# left.net
KiCad netlist of a schematic drawn in EAGLE
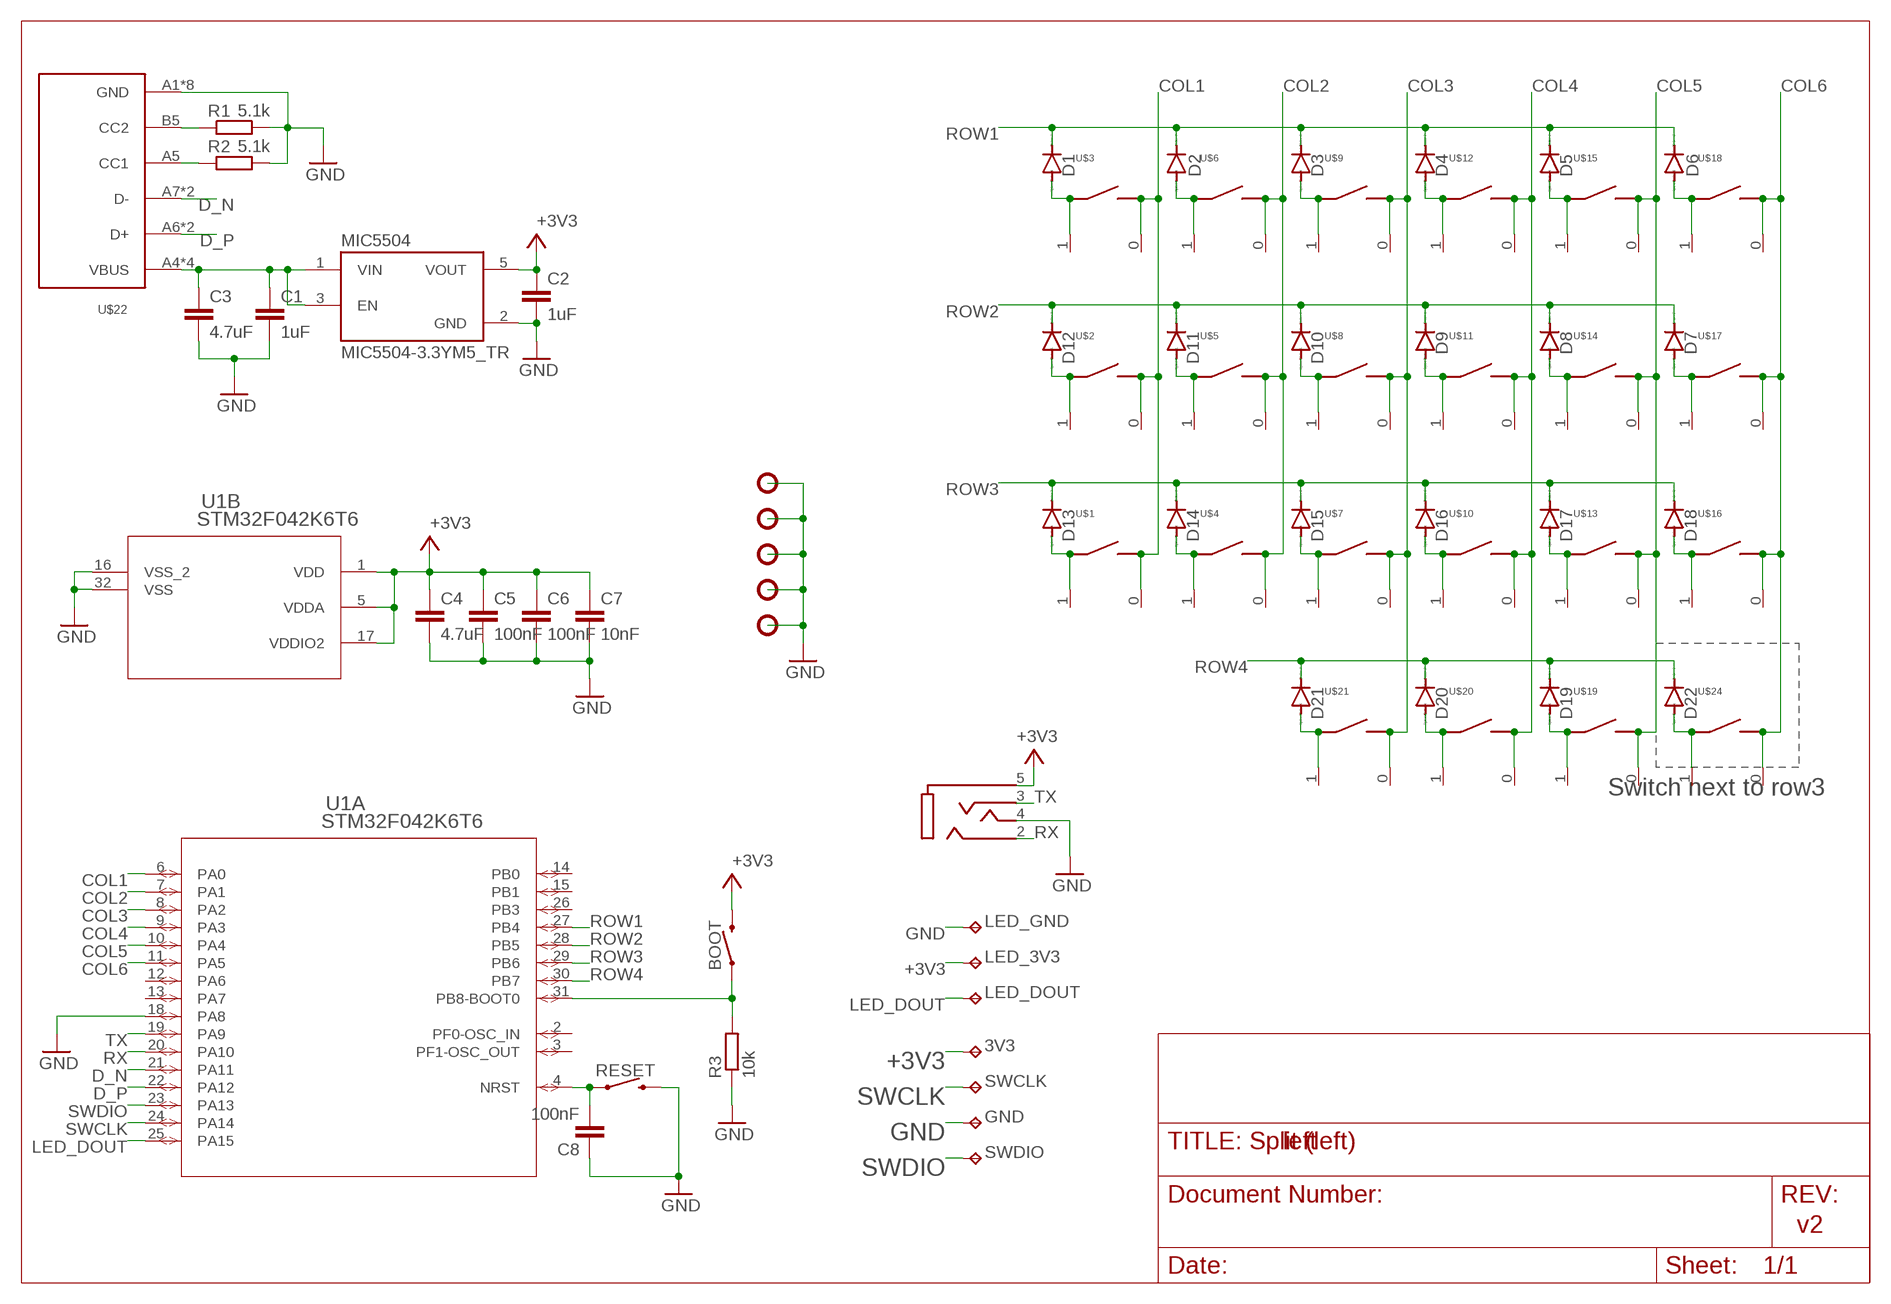
[diagram p0: schematic, sheet 1]

(export (version "E")
  (design (tool "Eeschema 10.0.6"))
  (components
    (comp (ref "3V3")
      (value "TPTP20R")
      (footprint "eagle-import:TP20R")
      (libsource (lib "eagle-import") (part "TPTP20R"))
    )
    (comp (ref "BOOT")
      (value "MOMENTARY-SWITCH-SPST-SMD-6.2MM-TALL")
      (footprint "eagle-import:TACTILE_SWITCH_SMD_6.2MM")
      (libsource (lib "eagle-import") (part "MOMENTARY-SWITCH-SPST-SMD-6.2MM-TALL"))
    )
    (comp (ref "C1")
      (value "1uF")
      (footprint "eagle-import:C0603")
      (libsource (lib "eagle-import") (part "C-EUC0603"))
    )
    (comp (ref "C2")
      (value "1uF")
      (footprint "eagle-import:C0603")
      (libsource (lib "eagle-import") (part "C-EUC0603"))
    )
    (comp (ref "C3")
      (value "4.7uF")
      (footprint "eagle-import:C0603")
      (libsource (lib "eagle-import") (part "C-EUC0603"))
    )
    (comp (ref "C4")
      (value "4.7uF")
      (footprint "eagle-import:C0603")
      (libsource (lib "eagle-import") (part "C-EUC0603"))
    )
    (comp (ref "C5")
      (value "100nF")
      (footprint "eagle-import:C0603")
      (libsource (lib "eagle-import") (part "C-EUC0603"))
    )
    (comp (ref "C6")
      (value "100nF")
      (footprint "eagle-import:C0603")
      (libsource (lib "eagle-import") (part "C-EUC0603"))
    )
    (comp (ref "C7")
      (value "10nF")
      (footprint "eagle-import:C0603")
      (libsource (lib "eagle-import") (part "C-EUC0603"))
    )
    (comp (ref "C8")
      (value "100nF")
      (footprint "eagle-import:C0603")
      (libsource (lib "eagle-import") (part "C-EUC0603"))
    )
    (comp (ref "D1")
      (value "DIODE-MINIMELF")
      (footprint "eagle-import:MINIMELF")
      (libsource (lib "eagle-import") (part "DIODE-MINIMELF"))
    )
    (comp (ref "D2")
      (value "DIODE-MINIMELF")
      (footprint "eagle-import:MINIMELF")
      (libsource (lib "eagle-import") (part "DIODE-MINIMELF"))
    )
    (comp (ref "D3")
      (value "DIODE-MINIMELF")
      (footprint "eagle-import:MINIMELF")
      (libsource (lib "eagle-import") (part "DIODE-MINIMELF"))
    )
    (comp (ref "D4")
      (value "DIODE-MINIMELF")
      (footprint "eagle-import:MINIMELF")
      (libsource (lib "eagle-import") (part "DIODE-MINIMELF"))
    )
    (comp (ref "D5")
      (value "DIODE-MINIMELF")
      (footprint "eagle-import:MINIMELF")
      (libsource (lib "eagle-import") (part "DIODE-MINIMELF"))
    )
    (comp (ref "D6")
      (value "DIODE-MINIMELF")
      (footprint "eagle-import:MINIMELF")
      (libsource (lib "eagle-import") (part "DIODE-MINIMELF"))
    )
    (comp (ref "D7")
      (value "DIODE-MINIMELF")
      (footprint "eagle-import:MINIMELF")
      (libsource (lib "eagle-import") (part "DIODE-MINIMELF"))
    )
    (comp (ref "D8")
      (value "DIODE-MINIMELF")
      (footprint "eagle-import:MINIMELF")
      (libsource (lib "eagle-import") (part "DIODE-MINIMELF"))
    )
    (comp (ref "D9")
      (value "DIODE-MINIMELF")
      (footprint "eagle-import:MINIMELF")
      (libsource (lib "eagle-import") (part "DIODE-MINIMELF"))
    )
    (comp (ref "D10")
      (value "DIODE-MINIMELF")
      (footprint "eagle-import:MINIMELF")
      (libsource (lib "eagle-import") (part "DIODE-MINIMELF"))
    )
    (comp (ref "D11")
      (value "DIODE-MINIMELF")
      (footprint "eagle-import:MINIMELF")
      (libsource (lib "eagle-import") (part "DIODE-MINIMELF"))
    )
    (comp (ref "D12")
      (value "DIODE-MINIMELF")
      (footprint "eagle-import:MINIMELF")
      (libsource (lib "eagle-import") (part "DIODE-MINIMELF"))
    )
    (comp (ref "D13")
      (value "DIODE-MINIMELF")
      (footprint "eagle-import:MINIMELF")
      (libsource (lib "eagle-import") (part "DIODE-MINIMELF"))
    )
    (comp (ref "D14")
      (value "DIODE-MINIMELF")
      (footprint "eagle-import:MINIMELF")
      (libsource (lib "eagle-import") (part "DIODE-MINIMELF"))
    )
    (comp (ref "D15")
      (value "DIODE-MINIMELF")
      (footprint "eagle-import:MINIMELF")
      (libsource (lib "eagle-import") (part "DIODE-MINIMELF"))
    )
    (comp (ref "D16")
      (value "DIODE-MINIMELF")
      (footprint "eagle-import:MINIMELF")
      (libsource (lib "eagle-import") (part "DIODE-MINIMELF"))
    )
    (comp (ref "D17")
      (value "DIODE-MINIMELF")
      (footprint "eagle-import:MINIMELF")
      (libsource (lib "eagle-import") (part "DIODE-MINIMELF"))
    )
    (comp (ref "D18")
      (value "DIODE-MINIMELF")
      (footprint "eagle-import:MINIMELF")
      (libsource (lib "eagle-import") (part "DIODE-MINIMELF"))
    )
    (comp (ref "D19")
      (value "DIODE-MINIMELF")
      (footprint "eagle-import:MINIMELF")
      (libsource (lib "eagle-import") (part "DIODE-MINIMELF"))
    )
    (comp (ref "D20")
      (value "DIODE-MINIMELF")
      (footprint "eagle-import:MINIMELF")
      (libsource (lib "eagle-import") (part "DIODE-MINIMELF"))
    )
    (comp (ref "D21")
      (value "DIODE-MINIMELF")
      (footprint "eagle-import:MINIMELF")
      (libsource (lib "eagle-import") (part "DIODE-MINIMELF"))
    )
    (comp (ref "D22")
      (value "DIODE-MINIMELF")
      (footprint "eagle-import:MINIMELF")
      (libsource (lib "eagle-import") (part "DIODE-MINIMELF"))
    )
    (comp (ref "GND")
      (value "TPTP20R")
      (footprint "eagle-import:TP20R")
      (libsource (lib "eagle-import") (part "TPTP20R"))
    )
    (comp (ref "LED_3V3")
      (value "TPTP20R")
      (footprint "eagle-import:TP20R")
      (libsource (lib "eagle-import") (part "TPTP20R"))
    )
    (comp (ref "LED_DOUT")
      (value "TPTP20R")
      (footprint "eagle-import:TP20R")
      (libsource (lib "eagle-import") (part "TPTP20R"))
    )
    (comp (ref "LED_GND")
      (value "TPTP20R")
      (footprint "eagle-import:TP20R")
      (libsource (lib "eagle-import") (part "TPTP20R"))
    )
    (comp (ref "MIC5504")
      (value "MIC5504-3.3YM5_TR")
      (footprint "eagle-import:SOT95P280X145-5N")
      (fields (field (name "MF") "Microchip") (field (name "MP") "MIC5504-3.3YM5 TR"))
      (libsource (lib "eagle-import") (part "MIC5504-3.3YM5_TR"))
    )
    (comp (ref "R1")
      (value "5.1k")
      (footprint "eagle-import:R0603")
      (libsource (lib "eagle-import") (part "R-EU_R0603"))
    )
    (comp (ref "R2")
      (value "5.1k")
      (footprint "eagle-import:R0603")
      (libsource (lib "eagle-import") (part "R-EU_R0603"))
    )
    (comp (ref "R3")
      (value "10k")
      (footprint "eagle-import:R0603")
      (libsource (lib "eagle-import") (part "R-EU_R0603"))
    )
    (comp (ref "RESET")
      (value "MOMENTARY-SWITCH-SPST-SMD-6.2MM-TALL")
      (footprint "eagle-import:TACTILE_SWITCH_SMD_6.2MM")
      (libsource (lib "eagle-import") (part "MOMENTARY-SWITCH-SPST-SMD-6.2MM-TALL"))
    )
    (comp (ref "SWCLK")
      (value "TPTP20R")
      (footprint "eagle-import:TP20R")
      (libsource (lib "eagle-import") (part "TPTP20R"))
    )
    (comp (ref "SWDIO")
      (value "TPTP20R")
      (footprint "eagle-import:TP20R")
      (libsource (lib "eagle-import") (part "TPTP20R"))
    )
    (comp (ref "U$1")
      (value "CHOC-CHOC-1U")
      (footprint "eagle-import:CHOC-1U")
      (libsource (lib "eagle-import") (part "CHOC-CHOC-1U"))
    )
    (comp (ref "U$2")
      (value "CHOC-CHOC-1U")
      (footprint "eagle-import:CHOC-1U")
      (libsource (lib "eagle-import") (part "CHOC-CHOC-1U"))
    )
    (comp (ref "U$3")
      (value "CHOC-CHOC-1U")
      (footprint "eagle-import:CHOC-1U")
      (libsource (lib "eagle-import") (part "CHOC-CHOC-1U"))
    )
    (comp (ref "U$4")
      (value "CHOC-CHOC-1U")
      (footprint "eagle-import:CHOC-1U")
      (libsource (lib "eagle-import") (part "CHOC-CHOC-1U"))
    )
    (comp (ref "U$5")
      (value "CHOC-CHOC-1U")
      (footprint "eagle-import:CHOC-1U")
      (libsource (lib "eagle-import") (part "CHOC-CHOC-1U"))
    )
    (comp (ref "U$6")
      (value "CHOC-CHOC-1U")
      (footprint "eagle-import:CHOC-1U")
      (libsource (lib "eagle-import") (part "CHOC-CHOC-1U"))
    )
    (comp (ref "U$7")
      (value "CHOC-CHOC-1U")
      (footprint "eagle-import:CHOC-1U")
      (libsource (lib "eagle-import") (part "CHOC-CHOC-1U"))
    )
    (comp (ref "U$8")
      (value "CHOC-CHOC-1U")
      (footprint "eagle-import:CHOC-1U")
      (libsource (lib "eagle-import") (part "CHOC-CHOC-1U"))
    )
    (comp (ref "U$9")
      (value "CHOC-CHOC-1U")
      (footprint "eagle-import:CHOC-1U")
      (libsource (lib "eagle-import") (part "CHOC-CHOC-1U"))
    )
    (comp (ref "U$10")
      (value "CHOC-CHOC-1U")
      (footprint "eagle-import:CHOC-1U")
      (libsource (lib "eagle-import") (part "CHOC-CHOC-1U"))
    )
    (comp (ref "U$11")
      (value "CHOC-CHOC-1U")
      (footprint "eagle-import:CHOC-1U")
      (libsource (lib "eagle-import") (part "CHOC-CHOC-1U"))
    )
    (comp (ref "U$12")
      (value "CHOC-CHOC-1U")
      (footprint "eagle-import:CHOC-1U")
      (libsource (lib "eagle-import") (part "CHOC-CHOC-1U"))
    )
    (comp (ref "U$13")
      (value "CHOC-CHOC-1U")
      (footprint "eagle-import:CHOC-1U")
      (libsource (lib "eagle-import") (part "CHOC-CHOC-1U"))
    )
    (comp (ref "U$14")
      (value "CHOC-CHOC-1U")
      (footprint "eagle-import:CHOC-1U")
      (libsource (lib "eagle-import") (part "CHOC-CHOC-1U"))
    )
    (comp (ref "U$15")
      (value "CHOC-CHOC-1U")
      (footprint "eagle-import:CHOC-1U")
      (libsource (lib "eagle-import") (part "CHOC-CHOC-1U"))
    )
    (comp (ref "U$16")
      (value "CHOC-CHOC-1U")
      (footprint "eagle-import:CHOC-1U")
      (libsource (lib "eagle-import") (part "CHOC-CHOC-1U"))
    )
    (comp (ref "U$17")
      (value "CHOC-CHOC-1U")
      (footprint "eagle-import:CHOC-1U")
      (libsource (lib "eagle-import") (part "CHOC-CHOC-1U"))
    )
    (comp (ref "U$18")
      (value "CHOC-CHOC-1U")
      (footprint "eagle-import:CHOC-1U")
      (libsource (lib "eagle-import") (part "CHOC-CHOC-1U"))
    )
    (comp (ref "U$19")
      (value "CHOC-CHOC-1U")
      (footprint "eagle-import:CHOC-1U")
      (libsource (lib "eagle-import") (part "CHOC-CHOC-1U"))
    )
    (comp (ref "U$20")
      (value "CHOC-CHOC-1U")
      (footprint "eagle-import:CHOC-1U")
      (libsource (lib "eagle-import") (part "CHOC-CHOC-1U"))
    )
    (comp (ref "U$21")
      (value "CHOC-CHOC-1U")
      (footprint "eagle-import:CHOC-1U")
      (libsource (lib "eagle-import") (part "CHOC-CHOC-1U"))
    )
    (comp (ref "U$22")
      (value "217B-AG01")
      (footprint "eagle-import:217B-AG01")
      (libsource (lib "eagle-import") (part "217B-AG01"))
    )
    (comp (ref "U$23")
      (value "PJ320A")
      (footprint "eagle-import:PJ320A")
      (libsource (lib "eagle-import") (part "PJ320A"))
    )
    (comp (ref "U$24")
      (value "CHOC-CHOC-1U")
      (footprint "eagle-import:CHOC-1U")
      (libsource (lib "eagle-import") (part "CHOC-CHOC-1U"))
    )
    (comp (ref "U$25")
      (value "SOCKET")
      (footprint "eagle-import:CHOC-SOCKET")
      (libsource (lib "eagle-import") (part "SOCKET"))
    )
    (comp (ref "U$26")
      (value "SOCKET")
      (footprint "eagle-import:CHOC-SOCKET")
      (libsource (lib "eagle-import") (part "SOCKET"))
    )
    (comp (ref "U$27")
      (value "SOCKET")
      (footprint "eagle-import:CHOC-SOCKET")
      (libsource (lib "eagle-import") (part "SOCKET"))
    )
    (comp (ref "U$28")
      (value "SOCKET")
      (footprint "eagle-import:CHOC-SOCKET")
      (libsource (lib "eagle-import") (part "SOCKET"))
    )
    (comp (ref "U$29")
      (value "SOCKET")
      (footprint "eagle-import:CHOC-SOCKET")
      (libsource (lib "eagle-import") (part "SOCKET"))
    )
    (comp (ref "U$30")
      (value "SOCKET")
      (footprint "eagle-import:CHOC-SOCKET")
      (libsource (lib "eagle-import") (part "SOCKET"))
    )
    (comp (ref "U$31")
      (value "SOCKET")
      (footprint "eagle-import:CHOC-SOCKET")
      (libsource (lib "eagle-import") (part "SOCKET"))
    )
    (comp (ref "U$32")
      (value "SOCKET")
      (footprint "eagle-import:CHOC-SOCKET")
      (libsource (lib "eagle-import") (part "SOCKET"))
    )
    (comp (ref "U$33")
      (value "SOCKET")
      (footprint "eagle-import:CHOC-SOCKET")
      (libsource (lib "eagle-import") (part "SOCKET"))
    )
    (comp (ref "U$34")
      (value "SOCKET")
      (footprint "eagle-import:CHOC-SOCKET")
      (libsource (lib "eagle-import") (part "SOCKET"))
    )
    (comp (ref "U$35")
      (value "SOCKET")
      (footprint "eagle-import:CHOC-SOCKET")
      (libsource (lib "eagle-import") (part "SOCKET"))
    )
    (comp (ref "U$36")
      (value "SOCKET")
      (footprint "eagle-import:CHOC-SOCKET")
      (libsource (lib "eagle-import") (part "SOCKET"))
    )
    (comp (ref "U$37")
      (value "SOCKET")
      (footprint "eagle-import:CHOC-SOCKET")
      (libsource (lib "eagle-import") (part "SOCKET"))
    )
    (comp (ref "U$38")
      (value "SOCKET")
      (footprint "eagle-import:CHOC-SOCKET")
      (libsource (lib "eagle-import") (part "SOCKET"))
    )
    (comp (ref "U$39")
      (value "SOCKET")
      (footprint "eagle-import:CHOC-SOCKET")
      (libsource (lib "eagle-import") (part "SOCKET"))
    )
    (comp (ref "U$40")
      (value "SOCKET")
      (footprint "eagle-import:CHOC-SOCKET")
      (libsource (lib "eagle-import") (part "SOCKET"))
    )
    (comp (ref "U$41")
      (value "SOCKET")
      (footprint "eagle-import:CHOC-SOCKET")
      (libsource (lib "eagle-import") (part "SOCKET"))
    )
    (comp (ref "U$42")
      (value "SOCKET")
      (footprint "eagle-import:CHOC-SOCKET")
      (libsource (lib "eagle-import") (part "SOCKET"))
    )
    (comp (ref "U$43")
      (value "SOCKET")
      (footprint "eagle-import:CHOC-SOCKET")
      (libsource (lib "eagle-import") (part "SOCKET"))
    )
    (comp (ref "U$44")
      (value "SOCKET")
      (footprint "eagle-import:CHOC-SOCKET")
      (libsource (lib "eagle-import") (part "SOCKET"))
    )
    (comp (ref "U$45")
      (value "SOCKET")
      (footprint "eagle-import:CHOC-SOCKET")
      (libsource (lib "eagle-import") (part "SOCKET"))
    )
    (comp (ref "U$46")
      (value "SOCKET")
      (footprint "eagle-import:CHOC-SOCKET")
      (libsource (lib "eagle-import") (part "SOCKET"))
    )
    (comp (ref "U$47")
      (value "MOUNTING-PADHOLE-M2-OFFSET")
      (footprint "eagle-import:HOLE-M2-OFFSET")
      (libsource (lib "eagle-import") (part "MOUNTING-PADHOLE-M2-OFFSET"))
    )
    (comp (ref "U$48")
      (value "MOUNTING-PADHOLE-M2-OFFSET")
      (footprint "eagle-import:HOLE-M2-OFFSET")
      (libsource (lib "eagle-import") (part "MOUNTING-PADHOLE-M2-OFFSET"))
    )
    (comp (ref "U$49")
      (value "MOUNTING-PADHOLE-M2-OFFSET")
      (footprint "eagle-import:HOLE-M2-OFFSET")
      (libsource (lib "eagle-import") (part "MOUNTING-PADHOLE-M2-OFFSET"))
    )
    (comp (ref "U$50")
      (value "MOUNTING-PADHOLE-M2-OFFSET")
      (footprint "eagle-import:HOLE-M2-OFFSET")
      (libsource (lib "eagle-import") (part "MOUNTING-PADHOLE-M2-OFFSET"))
    )
    (comp (ref "U$51")
      (value "MOUNTING-PADHOLE-M2-OFFSET")
      (footprint "eagle-import:HOLE-M2-OFFSET")
      (libsource (lib "eagle-import") (part "MOUNTING-PADHOLE-M2-OFFSET"))
    )
    (comp (ref "U1")
      (value "STM32F042K6T6")
      (footprint "eagle-import:LQFP-32")
      (fields (field (name "COPYRIGHT") "Copyright (C) 2018 Accelerated Designs. All rights reserved"))
      (libsource (lib "eagle-import") (part "STM32F042K6T6"))
    )
  )
  (nets
    (net (code "1") (name "+3V3") (class "Default")
      (node (ref "3V3") (pin "TP") (pinfunction "TP_TP") (pintype "input"))
      (node (ref "BOOT") (pin "B2") (pinfunction "2_B2") (pintype "passive"))
      (node (ref "C2") (pin "1") (pinfunction "1_1") (pintype "passive"))
      (node (ref "C4") (pin "1") (pinfunction "1_1") (pintype "passive"))
      (node (ref "C5") (pin "1") (pinfunction "1_1") (pintype "passive"))
      (node (ref "C6") (pin "1") (pinfunction "1_1") (pintype "passive"))
      (node (ref "C7") (pin "1") (pinfunction "1_1") (pintype "passive"))
      (node (ref "LED_3V3") (pin "TP") (pinfunction "TP_TP") (pintype "input"))
      (node (ref "MIC5504") (pin "5") (pinfunction "VOUT_5") (pintype "output"))
      (node (ref "U$23") (pin "5") (pinfunction "5_5") (pintype "bidirectional"))
      (node (ref "U1") (pin "1") (pinfunction "VDD_1") (pintype "power_in"))
      (node (ref "U1") (pin "17") (pinfunction "VDDIO2_17") (pintype "power_in"))
      (node (ref "U1") (pin "5") (pinfunction "VDDA_5") (pintype "power_in"))
    )
    (net (code "2") (name "/COL1") (class "Default")
      (node (ref "U$1") (pin "1") (pinfunction "P1_1") (pintype "bidirectional"))
      (node (ref "U$2") (pin "1") (pinfunction "P1_1") (pintype "bidirectional"))
      (node (ref "U$25") (pin "0") (pinfunction "0_0") (pintype "bidirectional"))
      (node (ref "U$3") (pin "1") (pinfunction "P1_1") (pintype "bidirectional"))
      (node (ref "U$30") (pin "0") (pinfunction "0_0") (pintype "bidirectional"))
      (node (ref "U$41") (pin "0") (pinfunction "0_0") (pintype "bidirectional"))
      (node (ref "U1") (pin "6") (pinfunction "PA0_6") (pintype "bidirectional"))
    )
    (net (code "3") (name "/COL2") (class "Default")
      (node (ref "U$26") (pin "0") (pinfunction "0_0") (pintype "bidirectional"))
      (node (ref "U$31") (pin "0") (pinfunction "0_0") (pintype "bidirectional"))
      (node (ref "U$4") (pin "1") (pinfunction "P1_1") (pintype "bidirectional"))
      (node (ref "U$42") (pin "0") (pinfunction "0_0") (pintype "bidirectional"))
      (node (ref "U$5") (pin "1") (pinfunction "P1_1") (pintype "bidirectional"))
      (node (ref "U$6") (pin "1") (pinfunction "P1_1") (pintype "bidirectional"))
      (node (ref "U1") (pin "7") (pinfunction "PA1_7") (pintype "bidirectional"))
    )
    (net (code "4") (name "/COL3") (class "Default")
      (node (ref "U$21") (pin "1") (pinfunction "P1_1") (pintype "bidirectional"))
      (node (ref "U$27") (pin "0") (pinfunction "0_0") (pintype "bidirectional"))
      (node (ref "U$32") (pin "0") (pinfunction "0_0") (pintype "bidirectional"))
      (node (ref "U$37") (pin "0") (pinfunction "0_0") (pintype "bidirectional"))
      (node (ref "U$43") (pin "0") (pinfunction "0_0") (pintype "bidirectional"))
      (node (ref "U$7") (pin "1") (pinfunction "P1_1") (pintype "bidirectional"))
      (node (ref "U$8") (pin "1") (pinfunction "P1_1") (pintype "bidirectional"))
      (node (ref "U$9") (pin "1") (pinfunction "P1_1") (pintype "bidirectional"))
      (node (ref "U1") (pin "8") (pinfunction "PA2_8") (pintype "bidirectional"))
    )
    (net (code "5") (name "/COL4") (class "Default")
      (node (ref "U$10") (pin "1") (pinfunction "P1_1") (pintype "bidirectional"))
      (node (ref "U$11") (pin "1") (pinfunction "P1_1") (pintype "bidirectional"))
      (node (ref "U$12") (pin "1") (pinfunction "P1_1") (pintype "bidirectional"))
      (node (ref "U$20") (pin "1") (pinfunction "P1_1") (pintype "bidirectional"))
      (node (ref "U$28") (pin "0") (pinfunction "0_0") (pintype "bidirectional"))
      (node (ref "U$33") (pin "0") (pinfunction "0_0") (pintype "bidirectional"))
      (node (ref "U$38") (pin "0") (pinfunction "0_0") (pintype "bidirectional"))
      (node (ref "U$44") (pin "0") (pinfunction "0_0") (pintype "bidirectional"))
      (node (ref "U1") (pin "9") (pinfunction "PA3_9") (pintype "bidirectional"))
    )
    (net (code "6") (name "/COL5") (class "Default")
      (node (ref "U$13") (pin "1") (pinfunction "P1_1") (pintype "bidirectional"))
      (node (ref "U$14") (pin "1") (pinfunction "P1_1") (pintype "bidirectional"))
      (node (ref "U$15") (pin "1") (pinfunction "P1_1") (pintype "bidirectional"))
      (node (ref "U$19") (pin "1") (pinfunction "P1_1") (pintype "bidirectional"))
      (node (ref "U$29") (pin "0") (pinfunction "0_0") (pintype "bidirectional"))
      (node (ref "U$34") (pin "0") (pinfunction "0_0") (pintype "bidirectional"))
      (node (ref "U$39") (pin "0") (pinfunction "0_0") (pintype "bidirectional"))
      (node (ref "U$45") (pin "0") (pinfunction "0_0") (pintype "bidirectional"))
      (node (ref "U1") (pin "10") (pinfunction "PA4_10") (pintype "bidirectional"))
    )
    (net (code "7") (name "/COL6") (class "Default")
      (node (ref "U$16") (pin "1") (pinfunction "P1_1") (pintype "bidirectional"))
      (node (ref "U$17") (pin "1") (pinfunction "P1_1") (pintype "bidirectional"))
      (node (ref "U$18") (pin "1") (pinfunction "P1_1") (pintype "bidirectional"))
      (node (ref "U$24") (pin "1") (pinfunction "P1_1") (pintype "bidirectional"))
      (node (ref "U$35") (pin "0") (pinfunction "0_0") (pintype "bidirectional"))
      (node (ref "U$36") (pin "0") (pinfunction "0_0") (pintype "bidirectional"))
      (node (ref "U$40") (pin "0") (pinfunction "0_0") (pintype "bidirectional"))
      (node (ref "U$46") (pin "0") (pinfunction "0_0") (pintype "bidirectional"))
      (node (ref "U1") (pin "11") (pinfunction "PA5_11") (pintype "bidirectional"))
    )
    (net (code "8") (name "/D_N") (class "Default")
      (node (ref "U$22") (pin "A7") (pinfunction "D-_A7") (pintype "bidirectional"))
      (node (ref "U$22") (pin "B7") (pinfunction "D-_B7") (pintype "bidirectional"))
      (node (ref "U1") (pin "21") (pinfunction "PA11_21") (pintype "bidirectional"))
    )
    (net (code "9") (name "/D_P") (class "Default")
      (node (ref "U$22") (pin "A6") (pinfunction "D+_A6") (pintype "bidirectional"))
      (node (ref "U$22") (pin "B6") (pinfunction "D+_B6") (pintype "bidirectional"))
      (node (ref "U1") (pin "22") (pinfunction "PA12_22") (pintype "bidirectional"))
    )
    (net (code "10") (name "/LED_DOUT") (class "Default")
      (node (ref "LED_DOUT") (pin "TP") (pinfunction "TP_TP") (pintype "input"))
      (node (ref "U1") (pin "25") (pinfunction "PA15_25") (pintype "bidirectional"))
    )
    (net (code "11") (name "/ROW1") (class "Default")
      (node (ref "D1") (pin "C") (pinfunction "C_C") (pintype "passive"))
      (node (ref "D2") (pin "C") (pinfunction "C_C") (pintype "passive"))
      (node (ref "D3") (pin "C") (pinfunction "C_C") (pintype "passive"))
      (node (ref "D4") (pin "C") (pinfunction "C_C") (pintype "passive"))
      (node (ref "D5") (pin "C") (pinfunction "C_C") (pintype "passive"))
      (node (ref "D6") (pin "C") (pinfunction "C_C") (pintype "passive"))
      (node (ref "U1") (pin "27") (pinfunction "PB4_27") (pintype "bidirectional"))
    )
    (net (code "12") (name "/ROW2") (class "Default")
      (node (ref "D10") (pin "C") (pinfunction "C_C") (pintype "passive"))
      (node (ref "D11") (pin "C") (pinfunction "C_C") (pintype "passive"))
      (node (ref "D12") (pin "C") (pinfunction "C_C") (pintype "passive"))
      (node (ref "D7") (pin "C") (pinfunction "C_C") (pintype "passive"))
      (node (ref "D8") (pin "C") (pinfunction "C_C") (pintype "passive"))
      (node (ref "D9") (pin "C") (pinfunction "C_C") (pintype "passive"))
      (node (ref "U1") (pin "28") (pinfunction "PB5_28") (pintype "bidirectional"))
    )
    (net (code "13") (name "/ROW3") (class "Default")
      (node (ref "D13") (pin "C") (pinfunction "C_C") (pintype "passive"))
      (node (ref "D14") (pin "C") (pinfunction "C_C") (pintype "passive"))
      (node (ref "D15") (pin "C") (pinfunction "C_C") (pintype "passive"))
      (node (ref "D16") (pin "C") (pinfunction "C_C") (pintype "passive"))
      (node (ref "D17") (pin "C") (pinfunction "C_C") (pintype "passive"))
      (node (ref "D18") (pin "C") (pinfunction "C_C") (pintype "passive"))
      (node (ref "U1") (pin "29") (pinfunction "PB6_29") (pintype "bidirectional"))
    )
    (net (code "14") (name "/ROW4") (class "Default")
      (node (ref "D19") (pin "C") (pinfunction "C_C") (pintype "passive"))
      (node (ref "D20") (pin "C") (pinfunction "C_C") (pintype "passive"))
      (node (ref "D21") (pin "C") (pinfunction "C_C") (pintype "passive"))
      (node (ref "D22") (pin "C") (pinfunction "C_C") (pintype "passive"))
      (node (ref "U1") (pin "30") (pinfunction "PB7_30") (pintype "bidirectional"))
    )
    (net (code "15") (name "/RX") (class "Default")
      (node (ref "U$23") (pin "2") (pinfunction "2_2") (pintype "bidirectional"))
      (node (ref "U1") (pin "20") (pinfunction "PA10_20") (pintype "bidirectional"))
    )
    (net (code "16") (name "/SWCLK") (class "Default")
      (node (ref "SWCLK") (pin "TP") (pinfunction "TP_TP") (pintype "input"))
      (node (ref "U1") (pin "24") (pinfunction "PA14_24") (pintype "bidirectional"))
    )
    (net (code "17") (name "/SWDIO") (class "Default")
      (node (ref "SWDIO") (pin "TP") (pinfunction "TP_TP") (pintype "input"))
      (node (ref "U1") (pin "23") (pinfunction "PA13_23") (pintype "bidirectional"))
    )
    (net (code "18") (name "/TX") (class "Default")
      (node (ref "U$23") (pin "3") (pinfunction "3_3") (pintype "bidirectional"))
      (node (ref "U1") (pin "19") (pinfunction "PA9_19") (pintype "bidirectional"))
    )
    (net (code "19") (name "GND") (class "Default")
      (node (ref "C1") (pin "2") (pinfunction "2_2") (pintype "passive"))
      (node (ref "C2") (pin "2") (pinfunction "2_2") (pintype "passive"))
      (node (ref "C3") (pin "2") (pinfunction "2_2") (pintype "passive"))
      (node (ref "C4") (pin "2") (pinfunction "2_2") (pintype "passive"))
      (node (ref "C5") (pin "2") (pinfunction "2_2") (pintype "passive"))
      (node (ref "C6") (pin "2") (pinfunction "2_2") (pintype "passive"))
      (node (ref "C7") (pin "2") (pinfunction "2_2") (pintype "passive"))
      (node (ref "C8") (pin "1") (pinfunction "1_1") (pintype "passive"))
      (node (ref "GND") (pin "TP") (pinfunction "TP_TP") (pintype "input"))
      (node (ref "LED_GND") (pin "TP") (pinfunction "TP_TP") (pintype "input"))
      (node (ref "MIC5504") (pin "2") (pinfunction "GND_2") (pintype "power_in"))
      (node (ref "R1") (pin "2") (pinfunction "2_2") (pintype "passive"))
      (node (ref "R2") (pin "2") (pinfunction "2_2") (pintype "passive"))
      (node (ref "R3") (pin "1") (pinfunction "1_1") (pintype "passive"))
      (node (ref "RESET") (pin "B2") (pinfunction "2_B2") (pintype "passive"))
      (node (ref "U$22") (pin "A1") (pinfunction "GND_A1") (pintype "power_in"))
      (node (ref "U$22") (pin "A12") (pinfunction "GND_A12") (pintype "power_in"))
      (node (ref "U$22") (pin "B1") (pinfunction "GND_B1") (pintype "power_in"))
      (node (ref "U$22") (pin "B12") (pinfunction "GND_B12") (pintype "power_in"))
      (node (ref "U$22") (pin "SHELL") (pinfunction "GND_SHELL") (pintype "power_in"))
      (node (ref "U$22") (pin "SHELL1") (pinfunction "GND_SHELL1") (pintype "power_in"))
      (node (ref "U$22") (pin "SHELL2") (pinfunction "GND_SHELL2") (pintype "power_in"))
      (node (ref "U$22") (pin "SHELL3") (pinfunction "GND_SHELL3") (pintype "power_in"))
      (node (ref "U$23") (pin "4") (pinfunction "4_4") (pintype "bidirectional"))
      (node (ref "U$47") (pin "P$1") (pinfunction "P_P$1") (pintype "bidirectional"))
      (node (ref "U$48") (pin "P$1") (pinfunction "P_P$1") (pintype "bidirectional"))
      (node (ref "U$49") (pin "P$1") (pinfunction "P_P$1") (pintype "bidirectional"))
      (node (ref "U$50") (pin "P$1") (pinfunction "P_P$1") (pintype "bidirectional"))
      (node (ref "U$51") (pin "P$1") (pinfunction "P_P$1") (pintype "bidirectional"))
      (node (ref "U1") (pin "16") (pinfunction "VSS_2_16") (pintype "power_in"))
      (node (ref "U1") (pin "18") (pinfunction "PA8_18") (pintype "bidirectional"))
      (node (ref "U1") (pin "32") (pinfunction "VSS_32") (pintype "power_in"))
    )
    (net (code "20") (name "Net-(BOOT-1)") (class "Default")
      (node (ref "BOOT") (pin "A2") (pinfunction "1_A2") (pintype "passive"))
      (node (ref "R3") (pin "2") (pinfunction "2_2") (pintype "passive"))
      (node (ref "U1") (pin "31") (pinfunction "PB8-BOOT0_31") (pintype "bidirectional"))
    )
    (net (code "21") (name "Net-(MIC5504-EN)") (class "Default")
      (node (ref "C1") (pin "1") (pinfunction "1_1") (pintype "passive"))
      (node (ref "C3") (pin "1") (pinfunction "1_1") (pintype "passive"))
      (node (ref "MIC5504") (pin "1") (pinfunction "VIN_1") (pintype "input"))
      (node (ref "MIC5504") (pin "3") (pinfunction "EN_3") (pintype "input"))
      (node (ref "U$22") (pin "A4") (pinfunction "VBUS_A4") (pintype "power_in"))
      (node (ref "U$22") (pin "A9") (pinfunction "VBUS_A9") (pintype "power_in"))
      (node (ref "U$22") (pin "B4") (pinfunction "VBUS_B4") (pintype "power_in"))
      (node (ref "U$22") (pin "B9") (pinfunction "VBUS_B9") (pintype "power_in"))
    )
    (net (code "22") (name "Net-(RESET-1)") (class "Default")
      (node (ref "C8") (pin "2") (pinfunction "2_2") (pintype "passive"))
      (node (ref "RESET") (pin "A2") (pinfunction "1_A2") (pintype "passive"))
      (node (ref "U1") (pin "4") (pinfunction "NRST_4") (pintype "bidirectional"))
    )
    (net (code "23") (name "Net-(U$1-P0)") (class "Default")
      (node (ref "D13") (pin "A") (pinfunction "A_A") (pintype "passive"))
      (node (ref "U$1") (pin "0") (pinfunction "P0_0") (pintype "bidirectional"))
      (node (ref "U$25") (pin "1") (pinfunction "1_1") (pintype "bidirectional"))
    )
    (net (code "24") (name "Net-(U$2-P0)") (class "Default")
      (node (ref "D12") (pin "A") (pinfunction "A_A") (pintype "passive"))
      (node (ref "U$2") (pin "0") (pinfunction "P0_0") (pintype "bidirectional"))
      (node (ref "U$30") (pin "1") (pinfunction "1_1") (pintype "bidirectional"))
    )
    (net (code "25") (name "Net-(U$3-P0)") (class "Default")
      (node (ref "D1") (pin "A") (pinfunction "A_A") (pintype "passive"))
      (node (ref "U$3") (pin "0") (pinfunction "P0_0") (pintype "bidirectional"))
      (node (ref "U$41") (pin "1") (pinfunction "1_1") (pintype "bidirectional"))
    )
    (net (code "26") (name "Net-(U$4-P0)") (class "Default")
      (node (ref "D14") (pin "A") (pinfunction "A_A") (pintype "passive"))
      (node (ref "U$26") (pin "1") (pinfunction "1_1") (pintype "bidirectional"))
      (node (ref "U$4") (pin "0") (pinfunction "P0_0") (pintype "bidirectional"))
    )
    (net (code "27") (name "Net-(U$5-P0)") (class "Default")
      (node (ref "D11") (pin "A") (pinfunction "A_A") (pintype "passive"))
      (node (ref "U$31") (pin "1") (pinfunction "1_1") (pintype "bidirectional"))
      (node (ref "U$5") (pin "0") (pinfunction "P0_0") (pintype "bidirectional"))
    )
    (net (code "28") (name "Net-(U$6-P0)") (class "Default")
      (node (ref "D2") (pin "A") (pinfunction "A_A") (pintype "passive"))
      (node (ref "U$42") (pin "1") (pinfunction "1_1") (pintype "bidirectional"))
      (node (ref "U$6") (pin "0") (pinfunction "P0_0") (pintype "bidirectional"))
    )
    (net (code "29") (name "Net-(U$7-P0)") (class "Default")
      (node (ref "D15") (pin "A") (pinfunction "A_A") (pintype "passive"))
      (node (ref "U$27") (pin "1") (pinfunction "1_1") (pintype "bidirectional"))
      (node (ref "U$7") (pin "0") (pinfunction "P0_0") (pintype "bidirectional"))
    )
    (net (code "30") (name "Net-(U$8-P0)") (class "Default")
      (node (ref "D10") (pin "A") (pinfunction "A_A") (pintype "passive"))
      (node (ref "U$32") (pin "1") (pinfunction "1_1") (pintype "bidirectional"))
      (node (ref "U$8") (pin "0") (pinfunction "P0_0") (pintype "bidirectional"))
    )
    (net (code "31") (name "Net-(U$9-P0)") (class "Default")
      (node (ref "D3") (pin "A") (pinfunction "A_A") (pintype "passive"))
      (node (ref "U$43") (pin "1") (pinfunction "1_1") (pintype "bidirectional"))
      (node (ref "U$9") (pin "0") (pinfunction "P0_0") (pintype "bidirectional"))
    )
    (net (code "32") (name "Net-(U$10-P0)") (class "Default")
      (node (ref "D16") (pin "A") (pinfunction "A_A") (pintype "passive"))
      (node (ref "U$10") (pin "0") (pinfunction "P0_0") (pintype "bidirectional"))
      (node (ref "U$28") (pin "1") (pinfunction "1_1") (pintype "bidirectional"))
    )
    (net (code "33") (name "Net-(U$11-P0)") (class "Default")
      (node (ref "D9") (pin "A") (pinfunction "A_A") (pintype "passive"))
      (node (ref "U$11") (pin "0") (pinfunction "P0_0") (pintype "bidirectional"))
      (node (ref "U$33") (pin "1") (pinfunction "1_1") (pintype "bidirectional"))
    )
    (net (code "34") (name "Net-(U$12-P0)") (class "Default")
      (node (ref "D4") (pin "A") (pinfunction "A_A") (pintype "passive"))
      (node (ref "U$12") (pin "0") (pinfunction "P0_0") (pintype "bidirectional"))
      (node (ref "U$44") (pin "1") (pinfunction "1_1") (pintype "bidirectional"))
    )
    (net (code "35") (name "Net-(U$13-P0)") (class "Default")
      (node (ref "D17") (pin "A") (pinfunction "A_A") (pintype "passive"))
      (node (ref "U$13") (pin "0") (pinfunction "P0_0") (pintype "bidirectional"))
      (node (ref "U$29") (pin "1") (pinfunction "1_1") (pintype "bidirectional"))
    )
    (net (code "36") (name "Net-(U$14-P0)") (class "Default")
      (node (ref "D8") (pin "A") (pinfunction "A_A") (pintype "passive"))
      (node (ref "U$14") (pin "0") (pinfunction "P0_0") (pintype "bidirectional"))
      (node (ref "U$34") (pin "1") (pinfunction "1_1") (pintype "bidirectional"))
    )
    (net (code "37") (name "Net-(U$15-P0)") (class "Default")
      (node (ref "D5") (pin "A") (pinfunction "A_A") (pintype "passive"))
      (node (ref "U$15") (pin "0") (pinfunction "P0_0") (pintype "bidirectional"))
      (node (ref "U$45") (pin "1") (pinfunction "1_1") (pintype "bidirectional"))
    )
    (net (code "38") (name "Net-(U$16-P0)") (class "Default")
      (node (ref "D18") (pin "A") (pinfunction "A_A") (pintype "passive"))
      (node (ref "U$16") (pin "0") (pinfunction "P0_0") (pintype "bidirectional"))
      (node (ref "U$36") (pin "1") (pinfunction "1_1") (pintype "bidirectional"))
    )
    (net (code "39") (name "Net-(U$17-P0)") (class "Default")
      (node (ref "D7") (pin "A") (pinfunction "A_A") (pintype "passive"))
      (node (ref "U$17") (pin "0") (pinfunction "P0_0") (pintype "bidirectional"))
      (node (ref "U$35") (pin "1") (pinfunction "1_1") (pintype "bidirectional"))
    )
    (net (code "40") (name "Net-(U$18-P0)") (class "Default")
      (node (ref "D6") (pin "A") (pinfunction "A_A") (pintype "passive"))
      (node (ref "U$18") (pin "0") (pinfunction "P0_0") (pintype "bidirectional"))
      (node (ref "U$46") (pin "1") (pinfunction "1_1") (pintype "bidirectional"))
    )
    (net (code "41") (name "Net-(U$19-P0)") (class "Default")
      (node (ref "D19") (pin "A") (pinfunction "A_A") (pintype "passive"))
      (node (ref "U$19") (pin "0") (pinfunction "P0_0") (pintype "bidirectional"))
      (node (ref "U$39") (pin "1") (pinfunction "1_1") (pintype "bidirectional"))
    )
    (net (code "42") (name "Net-(U$20-P0)") (class "Default")
      (node (ref "D20") (pin "A") (pinfunction "A_A") (pintype "passive"))
      (node (ref "U$20") (pin "0") (pinfunction "P0_0") (pintype "bidirectional"))
      (node (ref "U$38") (pin "1") (pinfunction "1_1") (pintype "bidirectional"))
    )
    (net (code "43") (name "Net-(U$21-P0)") (class "Default")
      (node (ref "D21") (pin "A") (pinfunction "A_A") (pintype "passive"))
      (node (ref "U$21") (pin "0") (pinfunction "P0_0") (pintype "bidirectional"))
      (node (ref "U$37") (pin "1") (pinfunction "1_1") (pintype "bidirectional"))
    )
    (net (code "44") (name "Net-(U$22-CC1)") (class "Default")
      (node (ref "R2") (pin "1") (pinfunction "1_1") (pintype "passive"))
      (node (ref "U$22") (pin "A5") (pinfunction "CC1_A5") (pintype "bidirectional"))
    )
    (net (code "45") (name "Net-(U$22-CC2)") (class "Default")
      (node (ref "R1") (pin "1") (pinfunction "1_1") (pintype "passive"))
      (node (ref "U$22") (pin "B5") (pinfunction "CC2_B5") (pintype "bidirectional"))
    )
    (net (code "46") (name "Net-(U$24-P0)") (class "Default")
      (node (ref "D22") (pin "A") (pinfunction "A_A") (pintype "passive"))
      (node (ref "U$24") (pin "0") (pinfunction "P0_0") (pintype "bidirectional"))
      (node (ref "U$40") (pin "1") (pinfunction "1_1") (pintype "bidirectional"))
    )
    (net (code "47") (name "unconnected-(U1A-PA6-Pad12)") (class "Default")
      (node (ref "U1") (pin "12") (pinfunction "PA6_12") (pintype "bidirectional"))
    )
    (net (code "48") (name "unconnected-(U1A-PA7-Pad13)") (class "Default")
      (node (ref "U1") (pin "13") (pinfunction "PA7_13") (pintype "bidirectional"))
    )
    (net (code "49") (name "unconnected-(U1A-PB0-Pad14)") (class "Default")
      (node (ref "U1") (pin "14") (pinfunction "PB0_14") (pintype "bidirectional"))
    )
    (net (code "50") (name "unconnected-(U1A-PB1-Pad15)") (class "Default")
      (node (ref "U1") (pin "15") (pinfunction "PB1_15") (pintype "bidirectional"))
    )
    (net (code "51") (name "unconnected-(U1A-PB3-Pad26)") (class "Default")
      (node (ref "U1") (pin "26") (pinfunction "PB3_26") (pintype "bidirectional"))
    )
    (net (code "52") (name "unconnected-(U1A-PF0-OSC_IN-Pad2)") (class "Default")
      (node (ref "U1") (pin "2") (pinfunction "PF0-OSC_IN_2") (pintype "bidirectional"))
    )
    (net (code "53") (name "unconnected-(U1A-PF1-OSC_OUT-Pad3)") (class "Default")
      (node (ref "U1") (pin "3") (pinfunction "PF1-OSC_OUT_3") (pintype "bidirectional"))
    )
  )
)
